# 4_Channel_Mixer_-_Modular.net
KiCad netlist of a schematic drawn in EAGLE
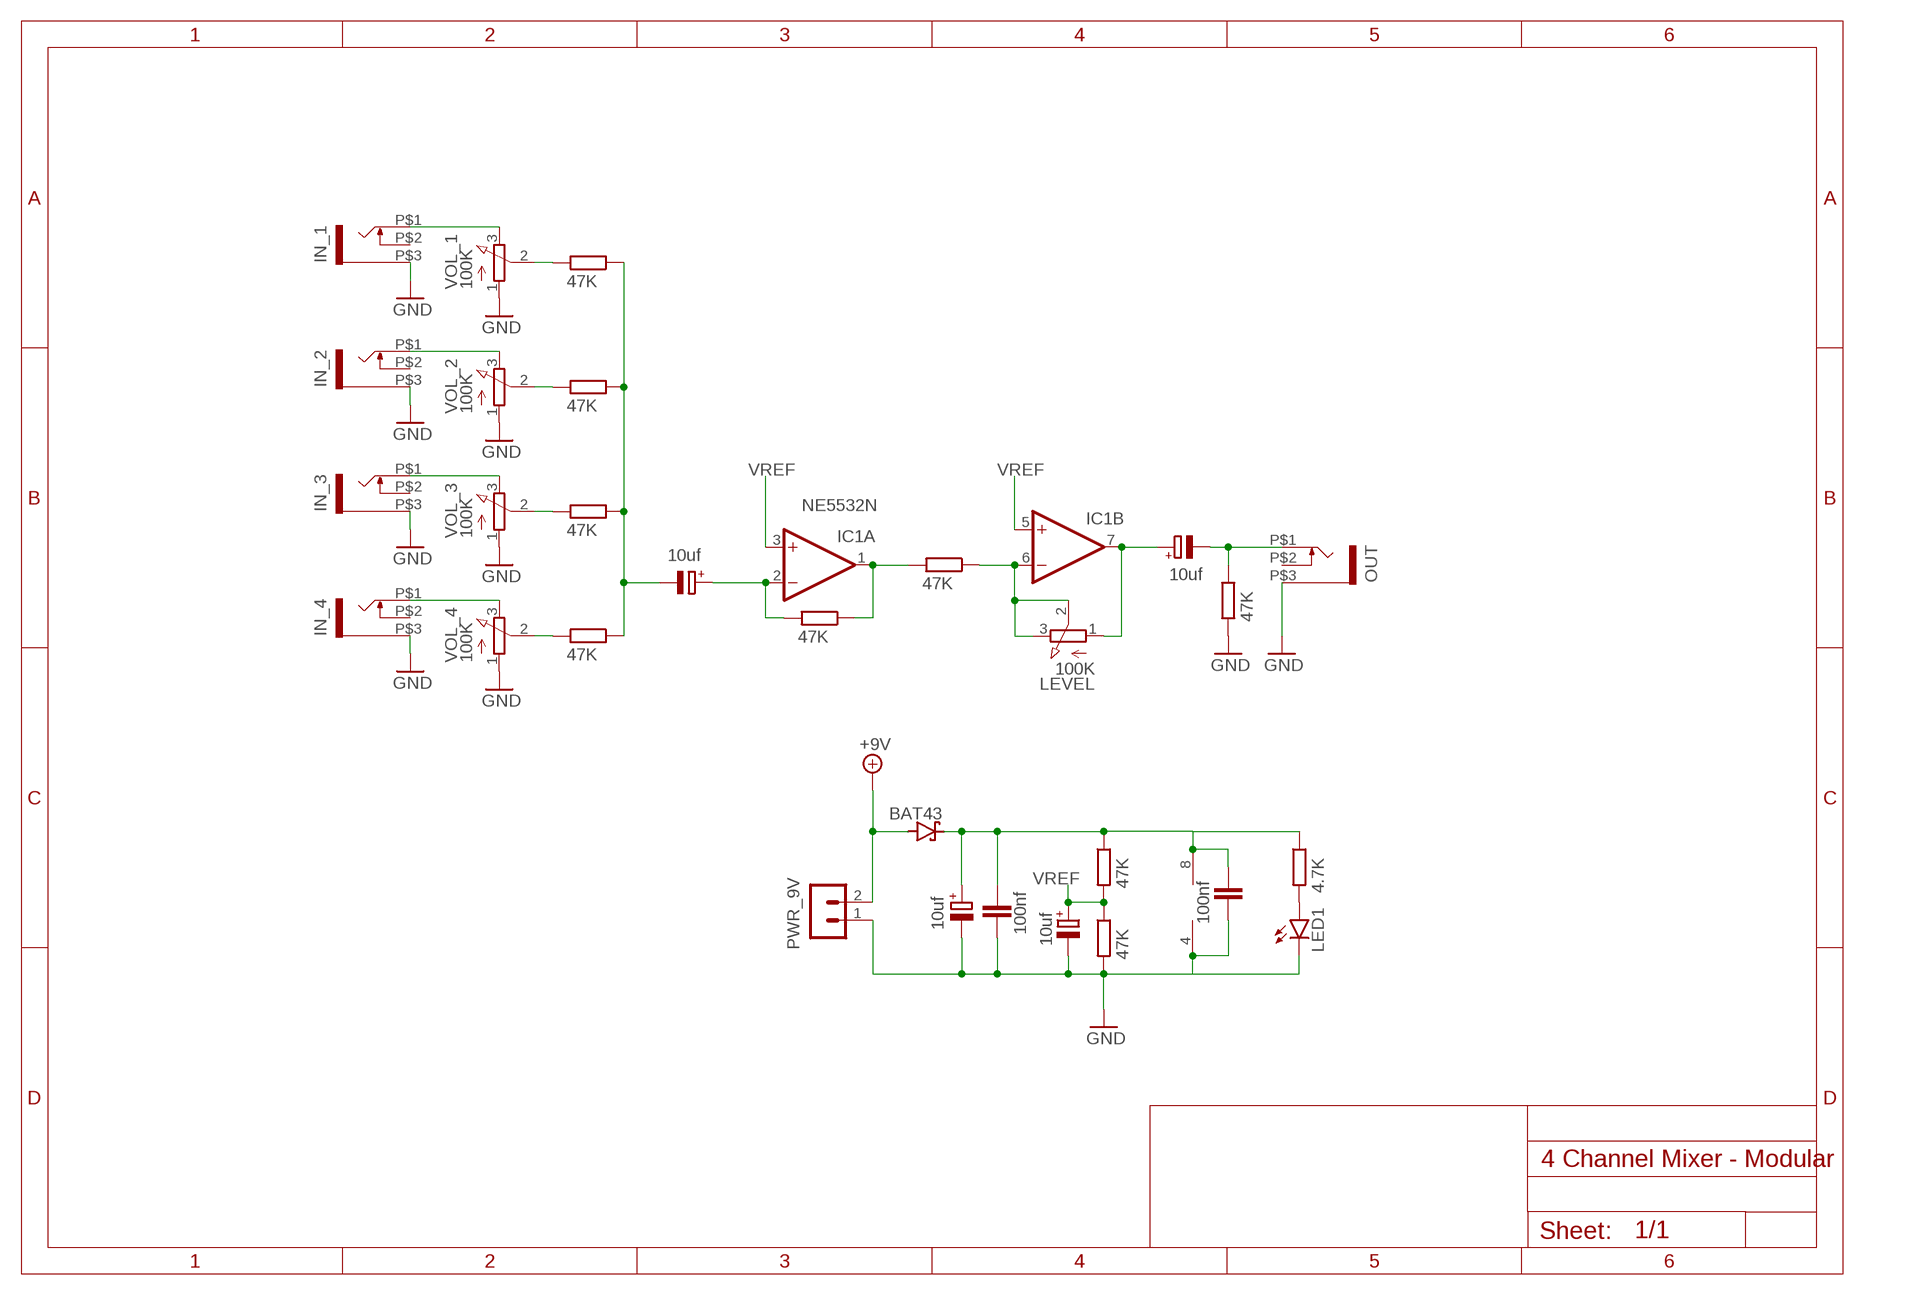
[diagram p0: schematic, sheet 1]

(export (version "E")
  (design (tool "Eeschema 10.0.6"))
  (components
    (comp (ref "C1")
      (value "10uf")
      (footprint "eagle-import:E2,5-6E")
      (libsource (lib "eagle-import") (part "CPOL-EUE2,5-6E"))
    )
    (comp (ref "C2")
      (value "10uf")
      (footprint "eagle-import:E2,5-6E")
      (libsource (lib "eagle-import") (part "CPOL-EUE2,5-6E"))
    )
    (comp (ref "C3")
      (value "10uf")
      (footprint "eagle-import:E2,5-6E")
      (libsource (lib "eagle-import") (part "CPOL-EUE2,5-6E"))
    )
    (comp (ref "C4")
      (value "10uf")
      (footprint "eagle-import:E2,5-6E")
      (libsource (lib "eagle-import") (part "CPOL-EUE2,5-6E"))
    )
    (comp (ref "C5")
      (value "100nf")
      (footprint "eagle-import:C050-024X044")
      (libsource (lib "eagle-import") (part "C-EU050-024X044"))
    )
    (comp (ref "C6")
      (value "100nf")
      (footprint "eagle-import:C050-024X044")
      (libsource (lib "eagle-import") (part "C-EU050-024X044"))
    )
    (comp (ref "D4")
      (value "BAT43")
      (footprint "eagle-import:DO35-10")
      (libsource (lib "eagle-import") (part "BAT42"))
    )
    (comp (ref "IC1")
      (value "NE5532N")
      (footprint "eagle-import:DIL08")
      (libsource (lib "eagle-import") (part "NE5532N"))
    )
    (comp (ref "IN_1")
      (value "WQP-PJ301M-12_JACK")
      (footprint "eagle-import:WQP-PJ301M-12_JACK")
      (libsource (lib "eagle-import") (part "WQP-PJ301M-12_JACK"))
    )
    (comp (ref "IN_2")
      (value "WQP-PJ301M-12_JACK")
      (footprint "eagle-import:WQP-PJ301M-12_JACK")
      (libsource (lib "eagle-import") (part "WQP-PJ301M-12_JACK"))
    )
    (comp (ref "IN_3")
      (value "WQP-PJ301M-12_JACK")
      (footprint "eagle-import:WQP-PJ301M-12_JACK")
      (libsource (lib "eagle-import") (part "WQP-PJ301M-12_JACK"))
    )
    (comp (ref "IN_4")
      (value "WQP-PJ301M-12_JACK")
      (footprint "eagle-import:WQP-PJ301M-12_JACK")
      (libsource (lib "eagle-import") (part "WQP-PJ301M-12_JACK"))
    )
    (comp (ref "LED1")
      (value "LED3MM")
      (footprint "eagle-import:LED3MM")
      (libsource (lib "eagle-import") (part "LED3MM"))
    )
    (comp (ref "LEVEL")
      (value "100K")
      (footprint "eagle-import:EVUFXM")
      (libsource (lib "eagle-import") (part "EVUMF2"))
    )
    (comp (ref "OUT")
      (value "WQP-PJ301M-12_JACK")
      (footprint "eagle-import:WQP-PJ301M-12_JACK")
      (libsource (lib "eagle-import") (part "WQP-PJ301M-12_JACK"))
    )
    (comp (ref "PWR_9V")
      (value "B2B-PH-K-S")
      (footprint "eagle-import:B2B-PH-K-S")
      (libsource (lib "eagle-import") (part "B2B-PH-K-S"))
    )
    (comp (ref "R1")
      (value "47K")
      (footprint "eagle-import:0204_7")
      (libsource (lib "eagle-import") (part "R-EU_0204/7"))
    )
    (comp (ref "R2")
      (value "47K")
      (footprint "eagle-import:0204_7")
      (libsource (lib "eagle-import") (part "R-EU_0204/7"))
    )
    (comp (ref "R3")
      (value "47K")
      (footprint "eagle-import:0204_7")
      (libsource (lib "eagle-import") (part "R-EU_0204/7"))
    )
    (comp (ref "R5")
      (value "47K")
      (footprint "eagle-import:0204_7")
      (libsource (lib "eagle-import") (part "R-EU_0204/7"))
    )
    (comp (ref "R7")
      (value "47K")
      (footprint "eagle-import:0204_7")
      (libsource (lib "eagle-import") (part "R-EU_0204/7"))
    )
    (comp (ref "R8")
      (value "47K")
      (footprint "eagle-import:0204_7")
      (libsource (lib "eagle-import") (part "R-EU_0204/7"))
    )
    (comp (ref "R9")
      (value "47K")
      (footprint "eagle-import:0204_7")
      (libsource (lib "eagle-import") (part "R-EU_0204/7"))
    )
    (comp (ref "R10")
      (value "47K")
      (footprint "eagle-import:0204_7")
      (libsource (lib "eagle-import") (part "R-EU_0204/7"))
    )
    (comp (ref "R11")
      (value "47K")
      (footprint "eagle-import:0204_7")
      (libsource (lib "eagle-import") (part "R-EU_0204/7"))
    )
    (comp (ref "R12")
      (value "4.7K")
      (footprint "eagle-import:0204_7")
      (libsource (lib "eagle-import") (part "R-EU_0204/7"))
    )
    (comp (ref "VOL_1")
      (value "100K")
      (footprint "eagle-import:EVUFXM")
      (libsource (lib "eagle-import") (part "EVUMF2"))
    )
    (comp (ref "VOL_2")
      (value "100K")
      (footprint "eagle-import:EVUFXM")
      (libsource (lib "eagle-import") (part "EVUMF2"))
    )
    (comp (ref "VOL_3")
      (value "100K")
      (footprint "eagle-import:EVUFXM")
      (libsource (lib "eagle-import") (part "EVUMF2"))
    )
    (comp (ref "VOL_4")
      (value "100K")
      (footprint "eagle-import:EVUFXM")
      (libsource (lib "eagle-import") (part "EVUMF2"))
    )
  )
  (nets
    (net (code "1") (name "+9V") (class "Default")
      (node (ref "D4") (pin "A") (pinfunction "A_A") (pintype "passive"))
      (node (ref "PWR_9V") (pin "2") (pinfunction "2_2") (pintype "passive"))
    )
    (net (code "2") (name "/VREF") (class "Default")
      (node (ref "C3") (pin "+") (pinfunction "+_+") (pintype "passive"))
      (node (ref "IC1") (pin "3") (pinfunction "+IN_3") (pintype "input"))
      (node (ref "IC1") (pin "5") (pinfunction "+IN_5") (pintype "input"))
      (node (ref "R10") (pin "2") (pinfunction "2_2") (pintype "passive"))
      (node (ref "R11") (pin "1") (pinfunction "1_1") (pintype "passive"))
    )
    (net (code "3") (name "GND") (class "Default")
      (node (ref "C3") (pin "-") (pinfunction "-_-") (pintype "passive"))
      (node (ref "C4") (pin "-") (pinfunction "-_-") (pintype "passive"))
      (node (ref "C5") (pin "1") (pinfunction "1_1") (pintype "passive"))
      (node (ref "C6") (pin "1") (pinfunction "1_1") (pintype "passive"))
      (node (ref "IC1") (pin "4") (pinfunction "V-_4") (pintype "power_in"))
      (node (ref "IN_1") (pin "P$3") (pinfunction "1_P$3") (pintype "passive"))
      (node (ref "IN_2") (pin "P$3") (pinfunction "1_P$3") (pintype "passive"))
      (node (ref "IN_3") (pin "P$3") (pinfunction "1_P$3") (pintype "passive"))
      (node (ref "IN_4") (pin "P$3") (pinfunction "1_P$3") (pintype "passive"))
      (node (ref "LED1") (pin "K") (pinfunction "C_K") (pintype "passive"))
      (node (ref "OUT") (pin "P$3") (pinfunction "1_P$3") (pintype "passive"))
      (node (ref "PWR_9V") (pin "1") (pinfunction "1_1") (pintype "passive"))
      (node (ref "R11") (pin "2") (pinfunction "2_2") (pintype "passive"))
      (node (ref "R9") (pin "2") (pinfunction "2_2") (pintype "passive"))
      (node (ref "VOL_1") (pin "1") (pinfunction "A_1") (pintype "passive"))
      (node (ref "VOL_2") (pin "1") (pinfunction "A_1") (pintype "passive"))
      (node (ref "VOL_3") (pin "1") (pinfunction "A_1") (pintype "passive"))
      (node (ref "VOL_4") (pin "1") (pinfunction "A_1") (pintype "passive"))
    )
    (net (code "4") (name "Net-(C1-Pad-)") (class "Default")
      (node (ref "C1") (pin "-") (pinfunction "-_-") (pintype "passive"))
      (node (ref "R1") (pin "1") (pinfunction "1_1") (pintype "passive"))
      (node (ref "R2") (pin "1") (pinfunction "1_1") (pintype "passive"))
      (node (ref "R3") (pin "1") (pinfunction "1_1") (pintype "passive"))
      (node (ref "R5") (pin "1") (pinfunction "1_1") (pintype "passive"))
    )
    (net (code "5") (name "Net-(IC1A--IN)") (class "Default")
      (node (ref "C1") (pin "+") (pinfunction "+_+") (pintype "passive"))
      (node (ref "IC1") (pin "2") (pinfunction "-IN_2") (pintype "input"))
      (node (ref "R7") (pin "2") (pinfunction "2_2") (pintype "passive"))
    )
    (net (code "6") (name "Net-(IC1A-OUT)") (class "Default")
      (node (ref "IC1") (pin "1") (pinfunction "OUT_1") (pintype "output"))
      (node (ref "R7") (pin "1") (pinfunction "1_1") (pintype "passive"))
      (node (ref "R8") (pin "2") (pinfunction "2_2") (pintype "passive"))
    )
    (net (code "7") (name "Net-(IC1B--IN)") (class "Default")
      (node (ref "IC1") (pin "6") (pinfunction "-IN_6") (pintype "input"))
      (node (ref "LEVEL") (pin "2") (pinfunction "S_2") (pintype "passive"))
      (node (ref "LEVEL") (pin "3") (pinfunction "E_3") (pintype "passive"))
      (node (ref "R8") (pin "1") (pinfunction "1_1") (pintype "passive"))
    )
    (net (code "8") (name "Net-(IC1B-OUT)") (class "Default")
      (node (ref "C2") (pin "+") (pinfunction "+_+") (pintype "passive"))
      (node (ref "IC1") (pin "7") (pinfunction "OUT_7") (pintype "output"))
      (node (ref "LEVEL") (pin "1") (pinfunction "A_1") (pintype "passive"))
    )
    (net (code "9") (name "Net-(IC1C-V+)") (class "Default")
      (node (ref "C4") (pin "+") (pinfunction "+_+") (pintype "passive"))
      (node (ref "C5") (pin "2") (pinfunction "2_2") (pintype "passive"))
      (node (ref "C6") (pin "2") (pinfunction "2_2") (pintype "passive"))
      (node (ref "D4") (pin "C") (pinfunction "C_C") (pintype "passive"))
      (node (ref "IC1") (pin "8") (pinfunction "V+_8") (pintype "power_in"))
      (node (ref "R10") (pin "1") (pinfunction "1_1") (pintype "passive"))
      (node (ref "R12") (pin "1") (pinfunction "1_1") (pintype "passive"))
    )
    (net (code "10") (name "Net-(IN_1-2)") (class "Default")
      (node (ref "IN_1") (pin "P$1") (pinfunction "2_P$1") (pintype "passive"))
      (node (ref "VOL_1") (pin "3") (pinfunction "E_3") (pintype "passive"))
    )
    (net (code "11") (name "Net-(IN_2-2)") (class "Default")
      (node (ref "IN_2") (pin "P$1") (pinfunction "2_P$1") (pintype "passive"))
      (node (ref "VOL_2") (pin "3") (pinfunction "E_3") (pintype "passive"))
    )
    (net (code "12") (name "Net-(IN_3-2)") (class "Default")
      (node (ref "IN_3") (pin "P$1") (pinfunction "2_P$1") (pintype "passive"))
      (node (ref "VOL_3") (pin "3") (pinfunction "E_3") (pintype "passive"))
    )
    (net (code "13") (name "Net-(IN_4-2)") (class "Default")
      (node (ref "IN_4") (pin "P$1") (pinfunction "2_P$1") (pintype "passive"))
      (node (ref "VOL_4") (pin "3") (pinfunction "E_3") (pintype "passive"))
    )
    (net (code "14") (name "Net-(LED1-PadA)") (class "Default")
      (node (ref "LED1") (pin "A") (pinfunction "A_A") (pintype "passive"))
      (node (ref "R12") (pin "2") (pinfunction "2_2") (pintype "passive"))
    )
    (net (code "15") (name "Net-(OUT-2)") (class "Default")
      (node (ref "C2") (pin "-") (pinfunction "-_-") (pintype "passive"))
      (node (ref "OUT") (pin "P$1") (pinfunction "2_P$1") (pintype "passive"))
      (node (ref "R9") (pin "1") (pinfunction "1_1") (pintype "passive"))
    )
    (net (code "16") (name "Net-(VOL_1-S)") (class "Default")
      (node (ref "R5") (pin "2") (pinfunction "2_2") (pintype "passive"))
      (node (ref "VOL_1") (pin "2") (pinfunction "S_2") (pintype "passive"))
    )
    (net (code "17") (name "Net-(VOL_2-S)") (class "Default")
      (node (ref "R1") (pin "2") (pinfunction "2_2") (pintype "passive"))
      (node (ref "VOL_2") (pin "2") (pinfunction "S_2") (pintype "passive"))
    )
    (net (code "18") (name "Net-(VOL_3-S)") (class "Default")
      (node (ref "R2") (pin "2") (pinfunction "2_2") (pintype "passive"))
      (node (ref "VOL_3") (pin "2") (pinfunction "S_2") (pintype "passive"))
    )
    (net (code "19") (name "Net-(VOL_4-S)") (class "Default")
      (node (ref "R3") (pin "2") (pinfunction "2_2") (pintype "passive"))
      (node (ref "VOL_4") (pin "2") (pinfunction "S_2") (pintype "passive"))
    )
    (net (code "20") (name "unconnected-(IN_1-3-PadP$2)") (class "Default")
      (node (ref "IN_1") (pin "P$2") (pinfunction "3_P$2") (pintype "passive"))
    )
    (net (code "21") (name "unconnected-(IN_2-3-PadP$2)") (class "Default")
      (node (ref "IN_2") (pin "P$2") (pinfunction "3_P$2") (pintype "passive"))
    )
    (net (code "22") (name "unconnected-(IN_3-3-PadP$2)") (class "Default")
      (node (ref "IN_3") (pin "P$2") (pinfunction "3_P$2") (pintype "passive"))
    )
    (net (code "23") (name "unconnected-(IN_4-3-PadP$2)") (class "Default")
      (node (ref "IN_4") (pin "P$2") (pinfunction "3_P$2") (pintype "passive"))
    )
    (net (code "24") (name "unconnected-(OUT-3-PadP$2)") (class "Default")
      (node (ref "OUT") (pin "P$2") (pinfunction "3_P$2") (pintype "passive"))
    )
  )
)
